# ACC_SensorBoard.net
KiCad netlist of a schematic drawn in EAGLE
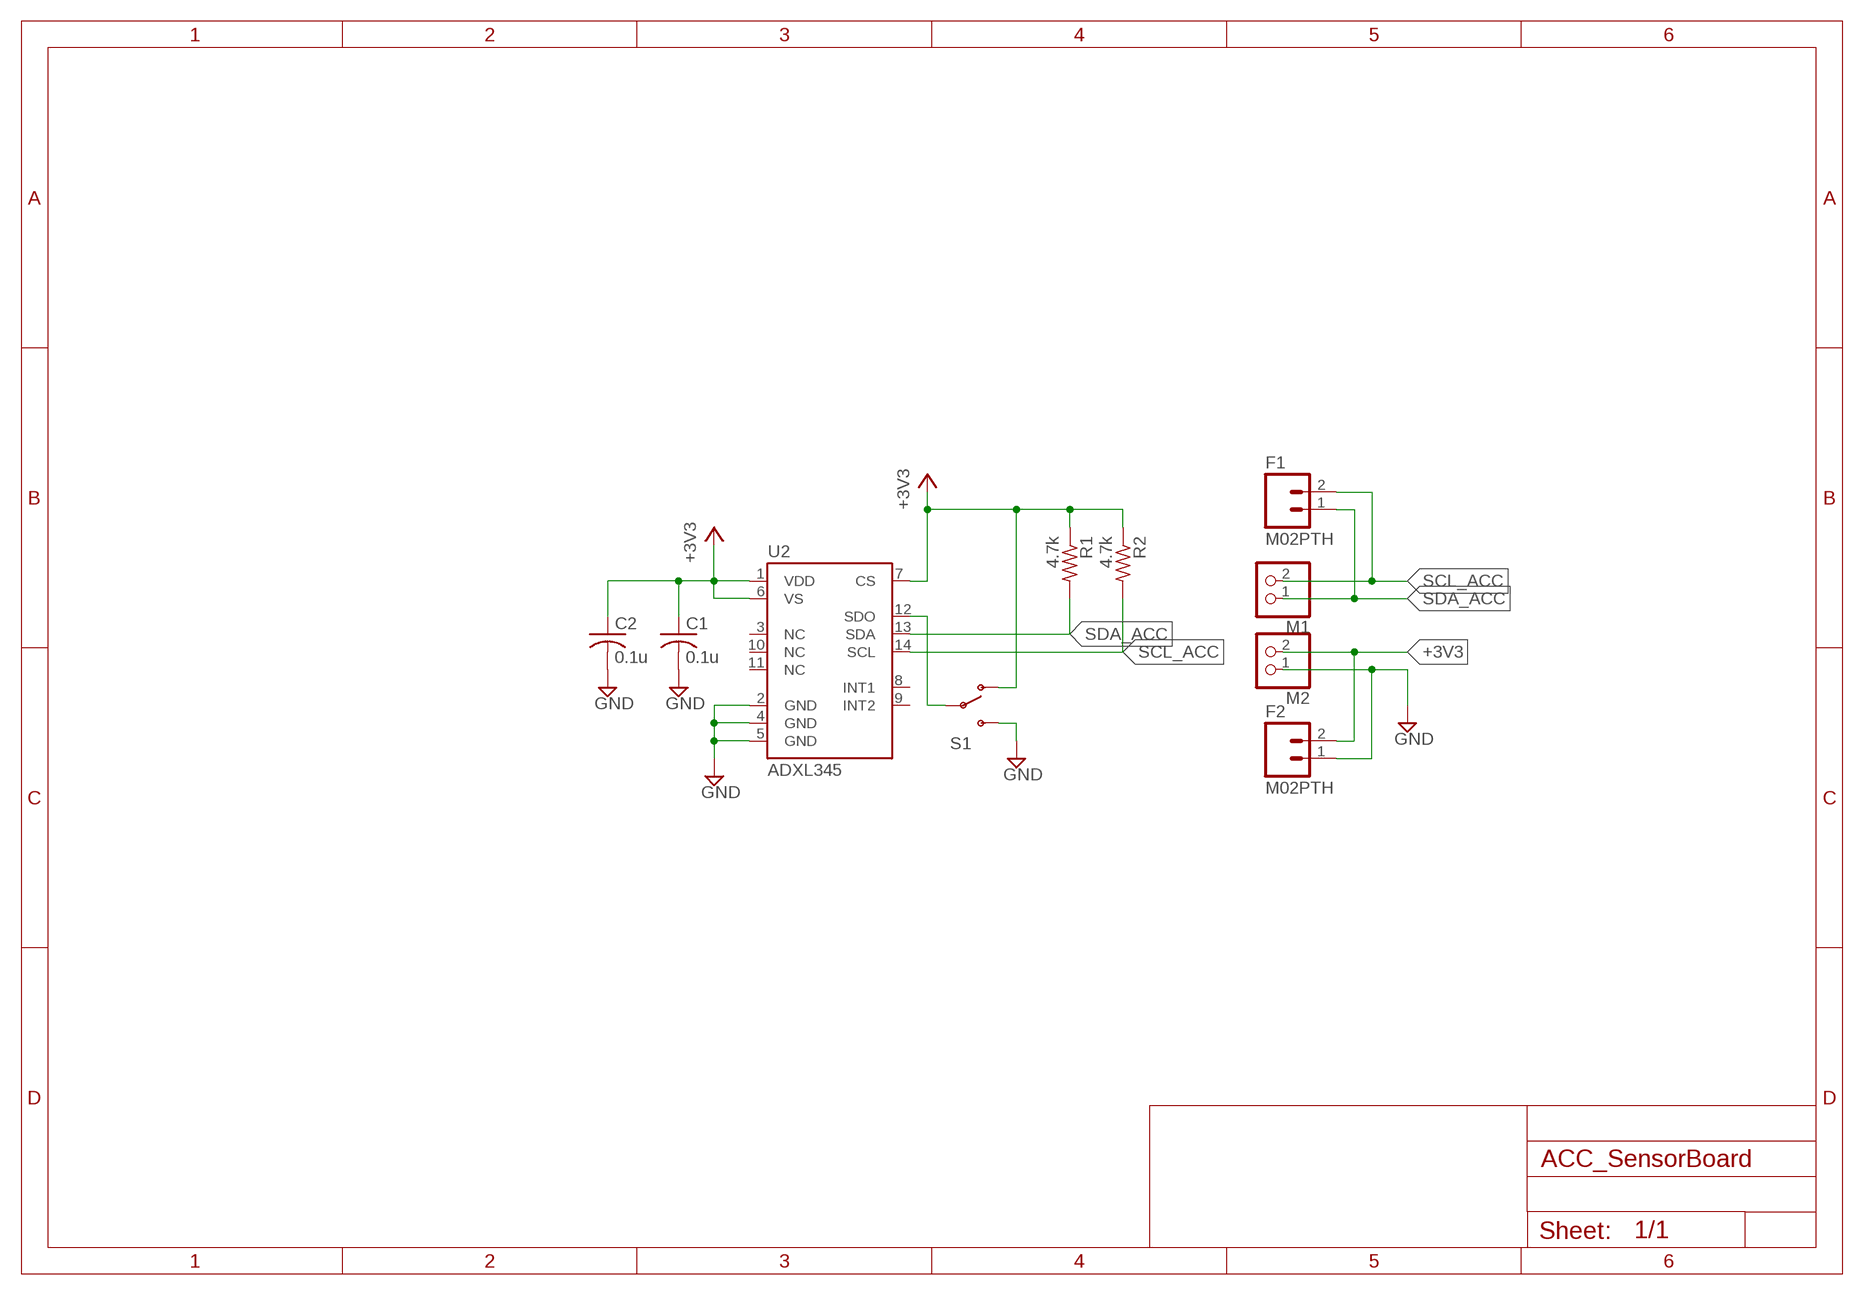
[diagram p0: schematic, sheet 1]

(export (version "E")
  (design (tool "Eeschema 10.0.6"))
  (components
    (comp (ref "C1")
      (value "0.1u")
      (footprint "eagle-import:C0805")
      (libsource (lib "eagle-import") (part "C-USC0805"))
    )
    (comp (ref "C2")
      (value "0.1u")
      (footprint "eagle-import:C0805")
      (libsource (lib "eagle-import") (part "C-USC0805"))
    )
    (comp (ref "F1")
      (value "M02PTH")
      (footprint "eagle-import:1X02")
      (libsource (lib "eagle-import") (part "M02PTH"))
    )
    (comp (ref "F2")
      (value "M02PTH")
      (footprint "eagle-import:1X02")
      (libsource (lib "eagle-import") (part "M02PTH"))
    )
    (comp (ref "M1")
      (value "PINHD-1X2")
      (footprint "eagle-import:1X02")
      (libsource (lib "eagle-import") (part "PINHD-1X2"))
    )
    (comp (ref "M2")
      (value "PINHD-1X2")
      (footprint "eagle-import:1X02")
      (libsource (lib "eagle-import") (part "PINHD-1X2"))
    )
    (comp (ref "R1")
      (value "4.7k")
      (footprint "eagle-import:R0805")
      (libsource (lib "eagle-import") (part "R-US_R0805"))
    )
    (comp (ref "R2")
      (value "4.7k")
      (footprint "eagle-import:R0805")
      (libsource (lib "eagle-import") (part "R-US_R0805"))
    )
    (comp (ref "S1")
      (value "SWITCH-SPDTSMD")
      (footprint "eagle-import:AYZ0202")
      (libsource (lib "eagle-import") (part "SWITCH-SPDTSMD"))
    )
    (comp (ref "U2")
      (value "ADXL345")
      (footprint "eagle-import:LGA14")
      (libsource (lib "eagle-import") (part "ADXL345"))
    )
  )
  (nets
    (net (code "1") (name "+3V3") (class "Default")
      (node (ref "C1") (pin "1") (pinfunction "1_1") (pintype "passive"))
      (node (ref "C2") (pin "1") (pinfunction "1_1") (pintype "passive"))
      (node (ref "F2") (pin "2") (pinfunction "2_2") (pintype "passive"))
      (node (ref "M2") (pin "2") (pinfunction "2_2") (pintype "passive"))
      (node (ref "R1") (pin "1") (pinfunction "1_1") (pintype "passive"))
      (node (ref "R2") (pin "1") (pinfunction "1_1") (pintype "passive"))
      (node (ref "S1") (pin "1") (pinfunction "O_1") (pintype "passive"))
      (node (ref "U2") (pin "1") (pinfunction "VDD_1") (pintype "bidirectional"))
      (node (ref "U2") (pin "6") (pinfunction "VS_6") (pintype "bidirectional"))
      (node (ref "U2") (pin "7") (pinfunction "CS_7") (pintype "bidirectional"))
    )
    (net (code "2") (name "GND") (class "Default")
      (node (ref "C1") (pin "2") (pinfunction "2_2") (pintype "passive"))
      (node (ref "C2") (pin "2") (pinfunction "2_2") (pintype "passive"))
      (node (ref "F2") (pin "1") (pinfunction "1_1") (pintype "passive"))
      (node (ref "M2") (pin "1") (pinfunction "1_1") (pintype "passive"))
      (node (ref "S1") (pin "3") (pinfunction "S_3") (pintype "passive"))
      (node (ref "U2") (pin "2") (pinfunction "GND_2") (pintype "bidirectional"))
      (node (ref "U2") (pin "4") (pinfunction "GND_4") (pintype "bidirectional"))
      (node (ref "U2") (pin "5") (pinfunction "GND_5") (pintype "bidirectional"))
    )
    (net (code "3") (name "Net-(S1-P)") (class "Default")
      (node (ref "S1") (pin "2") (pinfunction "P_2") (pintype "passive"))
      (node (ref "U2") (pin "12") (pinfunction "SDO_12") (pintype "bidirectional"))
    )
    (net (code "4") (name "SCL_ACC") (class "Default")
      (node (ref "F1") (pin "2") (pinfunction "2_2") (pintype "passive"))
      (node (ref "M1") (pin "2") (pinfunction "2_2") (pintype "passive"))
      (node (ref "R2") (pin "2") (pinfunction "2_2") (pintype "passive"))
      (node (ref "U2") (pin "14") (pinfunction "SCL_14") (pintype "bidirectional"))
    )
    (net (code "5") (name "SDA_ACC") (class "Default")
      (node (ref "F1") (pin "1") (pinfunction "1_1") (pintype "passive"))
      (node (ref "M1") (pin "1") (pinfunction "1_1") (pintype "passive"))
      (node (ref "R1") (pin "2") (pinfunction "2_2") (pintype "passive"))
      (node (ref "U2") (pin "13") (pinfunction "SDA_13") (pintype "bidirectional"))
    )
    (net (code "6") (name "unconnected-(U2-INT1-Pad8)") (class "Default")
      (node (ref "U2") (pin "8") (pinfunction "INT1_8") (pintype "bidirectional"))
    )
    (net (code "7") (name "unconnected-(U2-INT2-Pad9)") (class "Default")
      (node (ref "U2") (pin "9") (pinfunction "INT2_9") (pintype "bidirectional"))
    )
    (net (code "8") (name "unconnected-(U2-NC-Pad3)") (class "Default")
      (node (ref "U2") (pin "3") (pinfunction "NC_3") (pintype "bidirectional"))
    )
    (net (code "9") (name "unconnected-(U2-NC-Pad10)") (class "Default")
      (node (ref "U2") (pin "10") (pinfunction "NC_10") (pintype "bidirectional"))
    )
    (net (code "10") (name "unconnected-(U2-NC-Pad11)") (class "Default")
      (node (ref "U2") (pin "11") (pinfunction "NC_11") (pintype "bidirectional"))
    )
  )
)
